# S_Phase_Sense_Signal_Isolation.net
KiCad netlist of a schematic drawn in Altium Designer
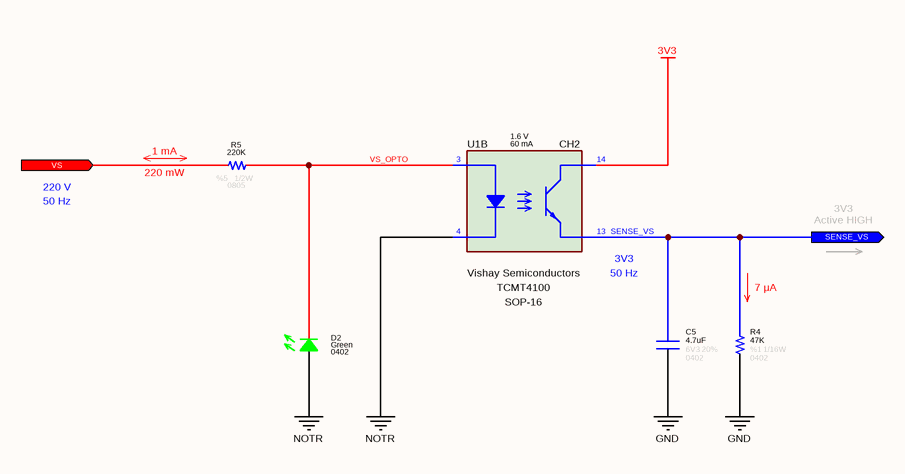
[diagram p0: S Phase Sense Signal Isolation.SchDoc]

(export (version "E")
  (design (tool "Eeschema 10.0.6"))
  (components
    (comp (ref "C5")
      (value "4.7uF")
      (footprint "CAPACITOR_0402")
      (description "Multilayer Ceramic Capacitors - SMD - 6V3 4.7uF X5R 0402 20%")
      (fields
        (field (name "MANUFACTURER PART NUMBER") "C0402C475M9PACTU")
        (field (name "TOLERANCE") "20%")
        (field (name "CASE") "0402")
        (field (name "VOLTAGE") "6V3")
        (field (name "Comment") "Capacitor - 4.7uF [0402] (Ceramic)")
      )
      (libsource (lib "Akkoyun") (part "Capacitor - 4.7uF [0402-6V3]"))
    )
    (comp (ref "D2")
      (value "SMD LED (Green)")
      (footprint "LED_0402")
      (description "Standard LEDs - SMD MINI-MOLD ULTRA COMPACT GREEN")
      (fields
        (field (name "MANUFACTURER PART NUMBER") "SML-P12MTT86R")
        (field (name "CASE") "0402")
        (field (name "COLOR") "Green")
      )
      (libsource (lib "Akkoyun") (part "Diode - LED (0402-Green)"))
    )
    (comp (ref "R4")
      (value "47K")
      (footprint "RESISTOR_0402")
      (description "Thick Film Resistors - SMD 1/16 W 47 KOhm 1%")
      (fields
        (field (name "MANUFACTURER PART NUMBER") "CRCW040247K0FKED")
        (field (name "TOLERANCE") "%1")
        (field (name "CASE") "0402")
        (field (name "POWER") "1/16W")
        (field (name "Comment") "47K - 0402 - %1 - 1/16W")
      )
      (libsource (lib "Akkoyun") (part "Resistor - 47K [0402]"))
    )
    (comp (ref "R5")
      (value "220K")
      (footprint "RESISTOR_0805")
      (description "Thick Film Resistors - SMD 1/2 W 220 KOhm 5%")
      (fields
        (field (name "MANUFACTURER PART NUMBER") "CRCW0805220KJNEAHP")
        (field (name "CASE") "0805")
        (field (name "TOLERANCE") "%5")
        (field (name "POWER") "1/2W")
        (field (name "Comment") "220K - 0805 - %5 - 1/16W")
      )
      (libsource (lib "Akkoyun") (part "Resistor - 220K [0805]"))
    )
    (comp (ref "U1")
      (value "TCMT4100")
      (footprint "SO-16")
      (description "OptpCoupler 4CH 16 Pin (SOP16)")
      (fields
        (field (name "IF - FORWARD CURRENT") "60 mA")
        (field (name "VF - FORWARD VOLTAGE") "1.6 V")
        (field (name "MANUFACTURER NAME") "Vishay Semiconductors")
        (field (name "MANUFACTURER PART NUMBER") "TCMT4100")
        (field (name "CASE") "SOP-16")
      )
      (libsource (lib "Akkoyun") (part "IC - TCMT4100"))
    )
  )
  (nets
    (net (code "1") (name "/SENSE_VS") (class "Default")
      (node (ref "C5") (pin "2") (pinfunction "2_2") (pintype "passive"))
      (node (ref "R4") (pin "2") (pinfunction "2_2") (pintype "passive"))
      (node (ref "U1") (pin "13") (pinfunction "Emiter_CH2_13") (pintype "open_emitter"))
    )
    (net (code "2") (name "/VS") (class "Default")
      (node (ref "R5") (pin "2") (pinfunction "2_2") (pintype "passive"))
    )
    (net (code "3") (name "/VS_OPTO") (class "Default")
      (node (ref "D2") (pin "1") (pinfunction "1_1") (pintype "passive"))
      (node (ref "R5") (pin "1") (pinfunction "1_1") (pintype "passive"))
      (node (ref "U1") (pin "3") (pinfunction "Anode_CH2_3") (pintype "passive"))
    )
    (net (code "4") (name "3V3") (class "Default")
      (node (ref "U1") (pin "14") (pinfunction "Collector_CH2_14") (pintype "passive"))
    )
    (net (code "5") (name "GND") (class "Default")
      (node (ref "C5") (pin "1") (pinfunction "1_1") (pintype "passive"))
      (node (ref "R4") (pin "1") (pinfunction "1_1") (pintype "passive"))
    )
    (net (code "6") (name "NOTR") (class "Default")
      (node (ref "D2") (pin "2") (pinfunction "2_2") (pintype "passive"))
      (node (ref "U1") (pin "4") (pinfunction "Cathode_CH2_4") (pintype "passive"))
    )
  )
)
